# timer_two_arduino.net
KiCad netlist of a schematic drawn in EAGLE
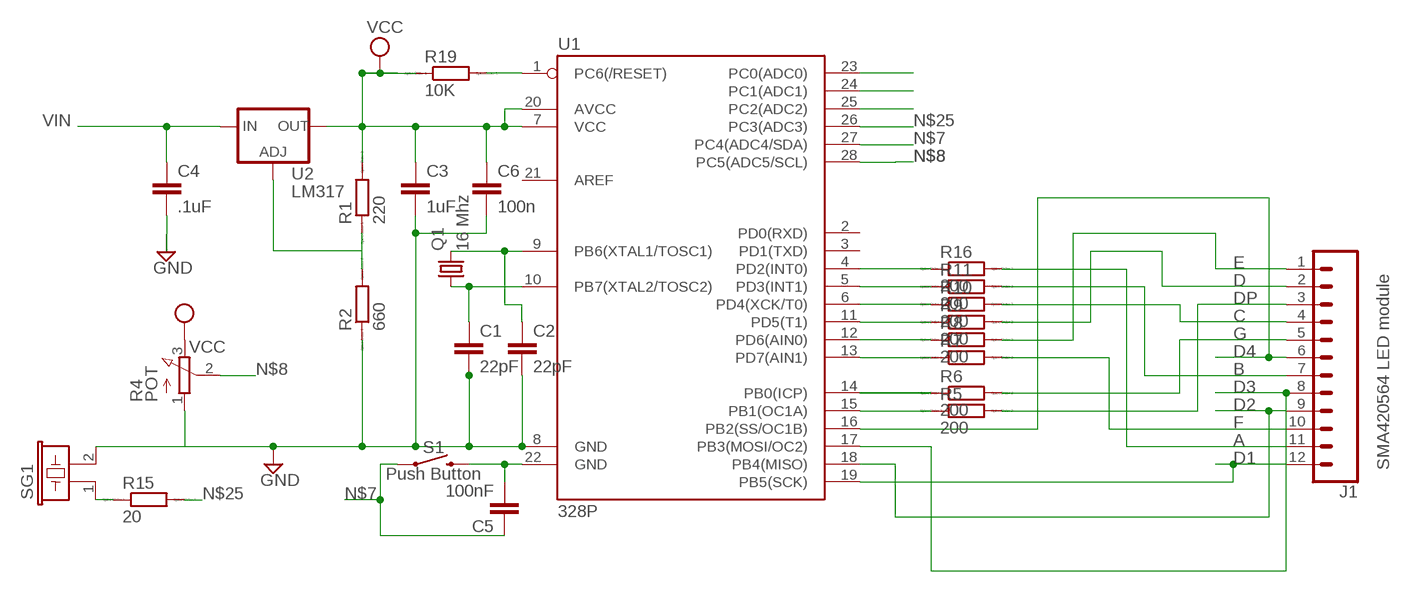
[diagram p0: schematic, sheet 1]

(export (version "E")
  (design (tool "Eeschema 10.0.6"))
  (components
    (comp (ref "C1")
      (value "22pF")
      (footprint "eagle-import:C2.5-3")
      (libsource (lib "eagle-import") (part "C2,5-3"))
    )
    (comp (ref "C2")
      (value "22pF")
      (footprint "eagle-import:C2.5-3")
      (libsource (lib "eagle-import") (part "C2,5-3"))
    )
    (comp (ref "C3")
      (value "1uF")
      (footprint "eagle-import:C2.5-3")
      (libsource (lib "eagle-import") (part "C2,5-3"))
    )
    (comp (ref "C4")
      (value ".1uF")
      (footprint "eagle-import:C2.5-3")
      (libsource (lib "eagle-import") (part "C2,5-3"))
    )
    (comp (ref "C5")
      (value "100nF")
      (footprint "eagle-import:C2.5-3")
      (libsource (lib "eagle-import") (part "C2,5-3"))
    )
    (comp (ref "C6")
      (value "100n")
      (footprint "eagle-import:C2.5-3")
      (libsource (lib "eagle-import") (part "C2,5-3"))
    )
    (comp (ref "J1")
      (value "SMA420564 LED module")
      (footprint "eagle-import:1X12")
      (libsource (lib "eagle-import") (part "CONN_12"))
    )
    (comp (ref "Q1")
      (value "16 Mhz")
      (footprint "eagle-import:HC18U-V")
      (libsource (lib "eagle-import") (part "CRYSTALHC18U-V"))
    )
    (comp (ref "R1")
      (value "220")
      (footprint "eagle-import:R2010")
      (libsource (lib "eagle-import") (part "RR2010"))
    )
    (comp (ref "R2")
      (value "660")
      (footprint "eagle-import:R2010")
      (libsource (lib "eagle-import") (part "RR2010"))
    )
    (comp (ref "R4")
      (value "POT")
      (footprint "eagle-import:3RP_1610N")
      (libsource (lib "eagle-import") (part "3RP/1610N"))
    )
    (comp (ref "R5")
      (value "200")
      (footprint "eagle-import:R0805")
      (libsource (lib "eagle-import") (part "R"))
    )
    (comp (ref "R6")
      (value "200")
      (footprint "eagle-import:R0805")
      (libsource (lib "eagle-import") (part "R"))
    )
    (comp (ref "R7") (value "R") (footprint "eagle-import:R0805") (libsource (lib "eagle-import") (part "R")))
    (comp (ref "R8")
      (value "200")
      (footprint "eagle-import:R0805")
      (libsource (lib "eagle-import") (part "R"))
    )
    (comp (ref "R9")
      (value "200")
      (footprint "eagle-import:R0805")
      (libsource (lib "eagle-import") (part "R"))
    )
    (comp (ref "R10")
      (value "200")
      (footprint "eagle-import:R0805")
      (libsource (lib "eagle-import") (part "R"))
    )
    (comp (ref "R11")
      (value "200")
      (footprint "eagle-import:R0805")
      (libsource (lib "eagle-import") (part "R"))
    )
    (comp (ref "R15")
      (value "20")
      (footprint "eagle-import:R0402")
      (libsource (lib "eagle-import") (part "RR0402"))
    )
    (comp (ref "R16")
      (value "200")
      (footprint "eagle-import:R0805")
      (libsource (lib "eagle-import") (part "R"))
    )
    (comp (ref "R19")
      (value "10K")
      (footprint "eagle-import:R0402")
      (libsource (lib "eagle-import") (part "RR0402"))
    )
    (comp (ref "S1")
      (value "Push Button")
      (footprint "eagle-import:TACTILE_SWITCH_PTH_6.0MM")
      (libsource (lib "eagle-import") (part "MOMENTARY-SWITCH-SPST-PTH-6.0MM"))
    )
    (comp (ref "SG1")
      (value "B/C11L")
      (footprint "eagle-import:B_C11L")
      (libsource (lib "eagle-import") (part "B/C11L"))
    )
    (comp (ref "U1")
      (value "328P")
      (footprint "eagle-import:DIP28")
      (libsource (lib "eagle-import") (part "ATMEGA328P_PDIP"))
    )
    (comp (ref "U2")
      (value "LM317")
      (footprint "eagle-import:V-REG_DPACK")
      (libsource (lib "eagle-import") (part "V_REG_317DPACK"))
    )
  )
  (nets
    (net (code "1") (name "/A") (class "Default")
      (node (ref "J1") (pin "11") (pinfunction "11_11") (pintype "passive"))
      (node (ref "R16") (pin "2") (pinfunction "2_2") (pintype "passive"))
    )
    (net (code "2") (name "/B") (class "Default")
      (node (ref "J1") (pin "7") (pinfunction "7_7") (pintype "passive"))
      (node (ref "R11") (pin "2") (pinfunction "2_2") (pintype "passive"))
    )
    (net (code "3") (name "/C") (class "Default")
      (node (ref "J1") (pin "4") (pinfunction "4_4") (pintype "passive"))
      (node (ref "R10") (pin "2") (pinfunction "2_2") (pintype "passive"))
    )
    (net (code "4") (name "/D") (class "Default")
      (node (ref "J1") (pin "2") (pinfunction "2_2") (pintype "passive"))
      (node (ref "R9") (pin "2") (pinfunction "2_2") (pintype "passive"))
    )
    (net (code "5") (name "/D1") (class "Default")
      (node (ref "J1") (pin "12") (pinfunction "12_12") (pintype "passive"))
      (node (ref "U1") (pin "19") (pinfunction "PB5(SCK)_19") (pintype "bidirectional"))
    )
    (net (code "6") (name "/D2") (class "Default")
      (node (ref "J1") (pin "9") (pinfunction "9_9") (pintype "passive"))
      (node (ref "U1") (pin "18") (pinfunction "PB4(MISO)_18") (pintype "bidirectional"))
    )
    (net (code "7") (name "/D3") (class "Default")
      (node (ref "J1") (pin "8") (pinfunction "8_8") (pintype "passive"))
      (node (ref "U1") (pin "17") (pinfunction "PB3(MOSI/OC2)_17") (pintype "bidirectional"))
    )
    (net (code "8") (name "/D4") (class "Default")
      (node (ref "J1") (pin "6") (pinfunction "6_6") (pintype "passive"))
      (node (ref "U1") (pin "16") (pinfunction "PB2(SS/OC1B)_16") (pintype "bidirectional"))
    )
    (net (code "9") (name "/DP") (class "Default")
      (node (ref "J1") (pin "3") (pinfunction "3_3") (pintype "passive"))
      (node (ref "R5") (pin "2") (pinfunction "2_2") (pintype "passive"))
    )
    (net (code "10") (name "/E") (class "Default")
      (node (ref "J1") (pin "1") (pinfunction "1_1") (pintype "passive"))
      (node (ref "R8") (pin "2") (pinfunction "2_2") (pintype "passive"))
    )
    (net (code "11") (name "/F") (class "Default")
      (node (ref "J1") (pin "10") (pinfunction "10_10") (pintype "passive"))
      (node (ref "R7") (pin "2") (pinfunction "2_2") (pintype "passive"))
    )
    (net (code "12") (name "/G") (class "Default")
      (node (ref "J1") (pin "5") (pinfunction "5_5") (pintype "passive"))
      (node (ref "R6") (pin "2") (pinfunction "2_2") (pintype "passive"))
    )
    (net (code "13") (name "/N$7") (class "Default")
      (node (ref "U1") (pin "27") (pinfunction "PC4(ADC4/SDA)_27") (pintype "bidirectional"))
    )
    (net (code "14") (name "/N$8") (class "Default")
      (node (ref "R4") (pin "2") (pinfunction "S_2") (pintype "passive"))
      (node (ref "U1") (pin "28") (pinfunction "PC5(ADC5/SCL)_28") (pintype "bidirectional"))
    )
    (net (code "15") (name "/N$25") (class "Default")
      (node (ref "R15") (pin "2") (pinfunction "2_2") (pintype "passive"))
    )
    (net (code "16") (name "/VIN") (class "Default")
      (node (ref "C4") (pin "1") (pinfunction "1_1") (pintype "passive"))
      (node (ref "U2") (pin "3") (pinfunction "IN_3") (pintype "input"))
    )
    (net (code "17") (name "GND") (class "Default")
      (node (ref "C1") (pin "2") (pinfunction "2_2") (pintype "passive"))
      (node (ref "C2") (pin "2") (pinfunction "2_2") (pintype "passive"))
      (node (ref "C3") (pin "2") (pinfunction "2_2") (pintype "passive"))
      (node (ref "C6") (pin "2") (pinfunction "2_2") (pintype "passive"))
      (node (ref "R2") (pin "1") (pinfunction "1_1") (pintype "passive"))
      (node (ref "R4") (pin "1") (pinfunction "A_1") (pintype "passive"))
      (node (ref "SG1") (pin "2") (pinfunction "2_2") (pintype "passive"))
      (node (ref "U1") (pin "8") (pinfunction "GND_8") (pintype "bidirectional"))
    )
    (net (code "18") (name "Net-(C5-Pad1)") (class "Default")
      (node (ref "C5") (pin "1") (pinfunction "1_1") (pintype "passive"))
      (node (ref "S1") (pin "1") (pinfunction "1_1") (pintype "passive"))
    )
    (net (code "19") (name "Net-(R1-Pad1)") (class "Default")
      (node (ref "R1") (pin "1") (pinfunction "1_1") (pintype "passive"))
      (node (ref "R2") (pin "2") (pinfunction "2_2") (pintype "passive"))
    )
    (net (code "20") (name "Net-(R15-Pad1)") (class "Default")
      (node (ref "R15") (pin "1") (pinfunction "1_1") (pintype "passive"))
      (node (ref "SG1") (pin "1") (pinfunction "1_1") (pintype "passive"))
    )
    (net (code "21") (name "Net-(S1-2)") (class "Default")
      (node (ref "C5") (pin "2") (pinfunction "2_2") (pintype "passive"))
      (node (ref "S1") (pin "3") (pinfunction "2_3") (pintype "passive"))
      (node (ref "U1") (pin "22") (pinfunction "GND_22") (pintype "bidirectional"))
    )
    (net (code "22") (name "Net-(U1-PB0(ICP))") (class "Default")
      (node (ref "R6") (pin "1") (pinfunction "1_1") (pintype "passive"))
      (node (ref "U1") (pin "14") (pinfunction "PB0(ICP)_14") (pintype "bidirectional"))
    )
    (net (code "23") (name "Net-(U1-PB1(OC1A))") (class "Default")
      (node (ref "R5") (pin "1") (pinfunction "1_1") (pintype "passive"))
      (node (ref "U1") (pin "15") (pinfunction "PB1(OC1A)_15") (pintype "bidirectional"))
    )
    (net (code "24") (name "Net-(U1-PB6(XTAL1{slash}TOSC1))") (class "Default")
      (node (ref "C2") (pin "1") (pinfunction "1_1") (pintype "passive"))
      (node (ref "Q1") (pin "2") (pinfunction "2_2") (pintype "passive"))
      (node (ref "U1") (pin "9") (pinfunction "PB6(XTAL1/TOSC1)_9") (pintype "bidirectional"))
    )
    (net (code "25") (name "Net-(U1-PB7(XTAL2{slash}TOSC2))") (class "Default")
      (node (ref "C1") (pin "1") (pinfunction "1_1") (pintype "passive"))
      (node (ref "Q1") (pin "1") (pinfunction "1_1") (pintype "passive"))
      (node (ref "U1") (pin "10") (pinfunction "PB7(XTAL2/TOSC2)_10") (pintype "bidirectional"))
    )
    (net (code "26") (name "Net-(U1-PC6({slash}RESET))") (class "Default")
      (node (ref "R19") (pin "2") (pinfunction "2_2") (pintype "passive"))
      (node (ref "U1") (pin "1") (pinfunction "PC6(/RESET)_1") (pintype "bidirectional"))
    )
    (net (code "27") (name "Net-(U1-PD2(INT0))") (class "Default")
      (node (ref "R16") (pin "1") (pinfunction "1_1") (pintype "passive"))
      (node (ref "U1") (pin "4") (pinfunction "PD2(INT0)_4") (pintype "bidirectional"))
    )
    (net (code "28") (name "Net-(U1-PD3(INT1))") (class "Default")
      (node (ref "R11") (pin "1") (pinfunction "1_1") (pintype "passive"))
      (node (ref "U1") (pin "5") (pinfunction "PD3(INT1)_5") (pintype "bidirectional"))
    )
    (net (code "29") (name "Net-(U1-PD4(XCK{slash}T0))") (class "Default")
      (node (ref "R10") (pin "1") (pinfunction "1_1") (pintype "passive"))
      (node (ref "U1") (pin "6") (pinfunction "PD4(XCK/T0)_6") (pintype "bidirectional"))
    )
    (net (code "30") (name "Net-(U1-PD5(T1))") (class "Default")
      (node (ref "R9") (pin "1") (pinfunction "1_1") (pintype "passive"))
      (node (ref "U1") (pin "11") (pinfunction "PD5(T1)_11") (pintype "bidirectional"))
    )
    (net (code "31") (name "Net-(U1-PD6(AIN0))") (class "Default")
      (node (ref "R8") (pin "1") (pinfunction "1_1") (pintype "passive"))
      (node (ref "U1") (pin "12") (pinfunction "PD6(AIN0)_12") (pintype "bidirectional"))
    )
    (net (code "32") (name "Net-(U1-PD7(AIN1))") (class "Default")
      (node (ref "R7") (pin "1") (pinfunction "1_1") (pintype "passive"))
      (node (ref "U1") (pin "13") (pinfunction "PD7(AIN1)_13") (pintype "bidirectional"))
    )
    (net (code "33") (name "VCC") (class "Default")
      (node (ref "C3") (pin "1") (pinfunction "1_1") (pintype "passive"))
      (node (ref "C6") (pin "1") (pinfunction "1_1") (pintype "passive"))
      (node (ref "R1") (pin "2") (pinfunction "2_2") (pintype "passive"))
      (node (ref "R19") (pin "1") (pinfunction "1_1") (pintype "passive"))
      (node (ref "R4") (pin "3") (pinfunction "E_3") (pintype "passive"))
      (node (ref "U1") (pin "20") (pinfunction "AVCC_20") (pintype "bidirectional"))
      (node (ref "U1") (pin "7") (pinfunction "VCC_7") (pintype "bidirectional"))
      (node (ref "U2") (pin "4") (pinfunction "OUT_4") (pintype "output"))
    )
    (net (code "34") (name "unconnected-(C4-Pad2)") (class "Default")
      (node (ref "C4") (pin "2") (pinfunction "2_2") (pintype "passive"))
    )
    (net (code "35") (name "unconnected-(U1-AREF-Pad21)") (class "Default")
      (node (ref "U1") (pin "21") (pinfunction "AREF_21") (pintype "bidirectional"))
    )
    (net (code "36") (name "unconnected-(U1-PC0(ADC0)-Pad23)") (class "Default")
      (node (ref "U1") (pin "23") (pinfunction "PC0(ADC0)_23") (pintype "bidirectional"))
    )
    (net (code "37") (name "unconnected-(U1-PC1(ADC1)-Pad24)") (class "Default")
      (node (ref "U1") (pin "24") (pinfunction "PC1(ADC1)_24") (pintype "bidirectional"))
    )
    (net (code "38") (name "unconnected-(U1-PC2(ADC2)-Pad25)") (class "Default")
      (node (ref "U1") (pin "25") (pinfunction "PC2(ADC2)_25") (pintype "bidirectional"))
    )
    (net (code "39") (name "unconnected-(U1-PC3(ADC3)-Pad26)") (class "Default")
      (node (ref "U1") (pin "26") (pinfunction "PC3(ADC3)_26") (pintype "bidirectional"))
    )
    (net (code "40") (name "unconnected-(U1-PD0(RXD)-Pad2)") (class "Default")
      (node (ref "U1") (pin "2") (pinfunction "PD0(RXD)_2") (pintype "bidirectional"))
    )
    (net (code "41") (name "unconnected-(U1-PD1(TXD)-Pad3)") (class "Default")
      (node (ref "U1") (pin "3") (pinfunction "PD1(TXD)_3") (pintype "bidirectional"))
    )
    (net (code "42") (name "unconnected-(U2-ADJ-Pad1)") (class "Default")
      (node (ref "U2") (pin "1") (pinfunction "ADJ_1") (pintype "input"))
    )
  )
)
